# Integrators_SarSol.net
KiCad netlist of a schematic drawn in Altium Designer
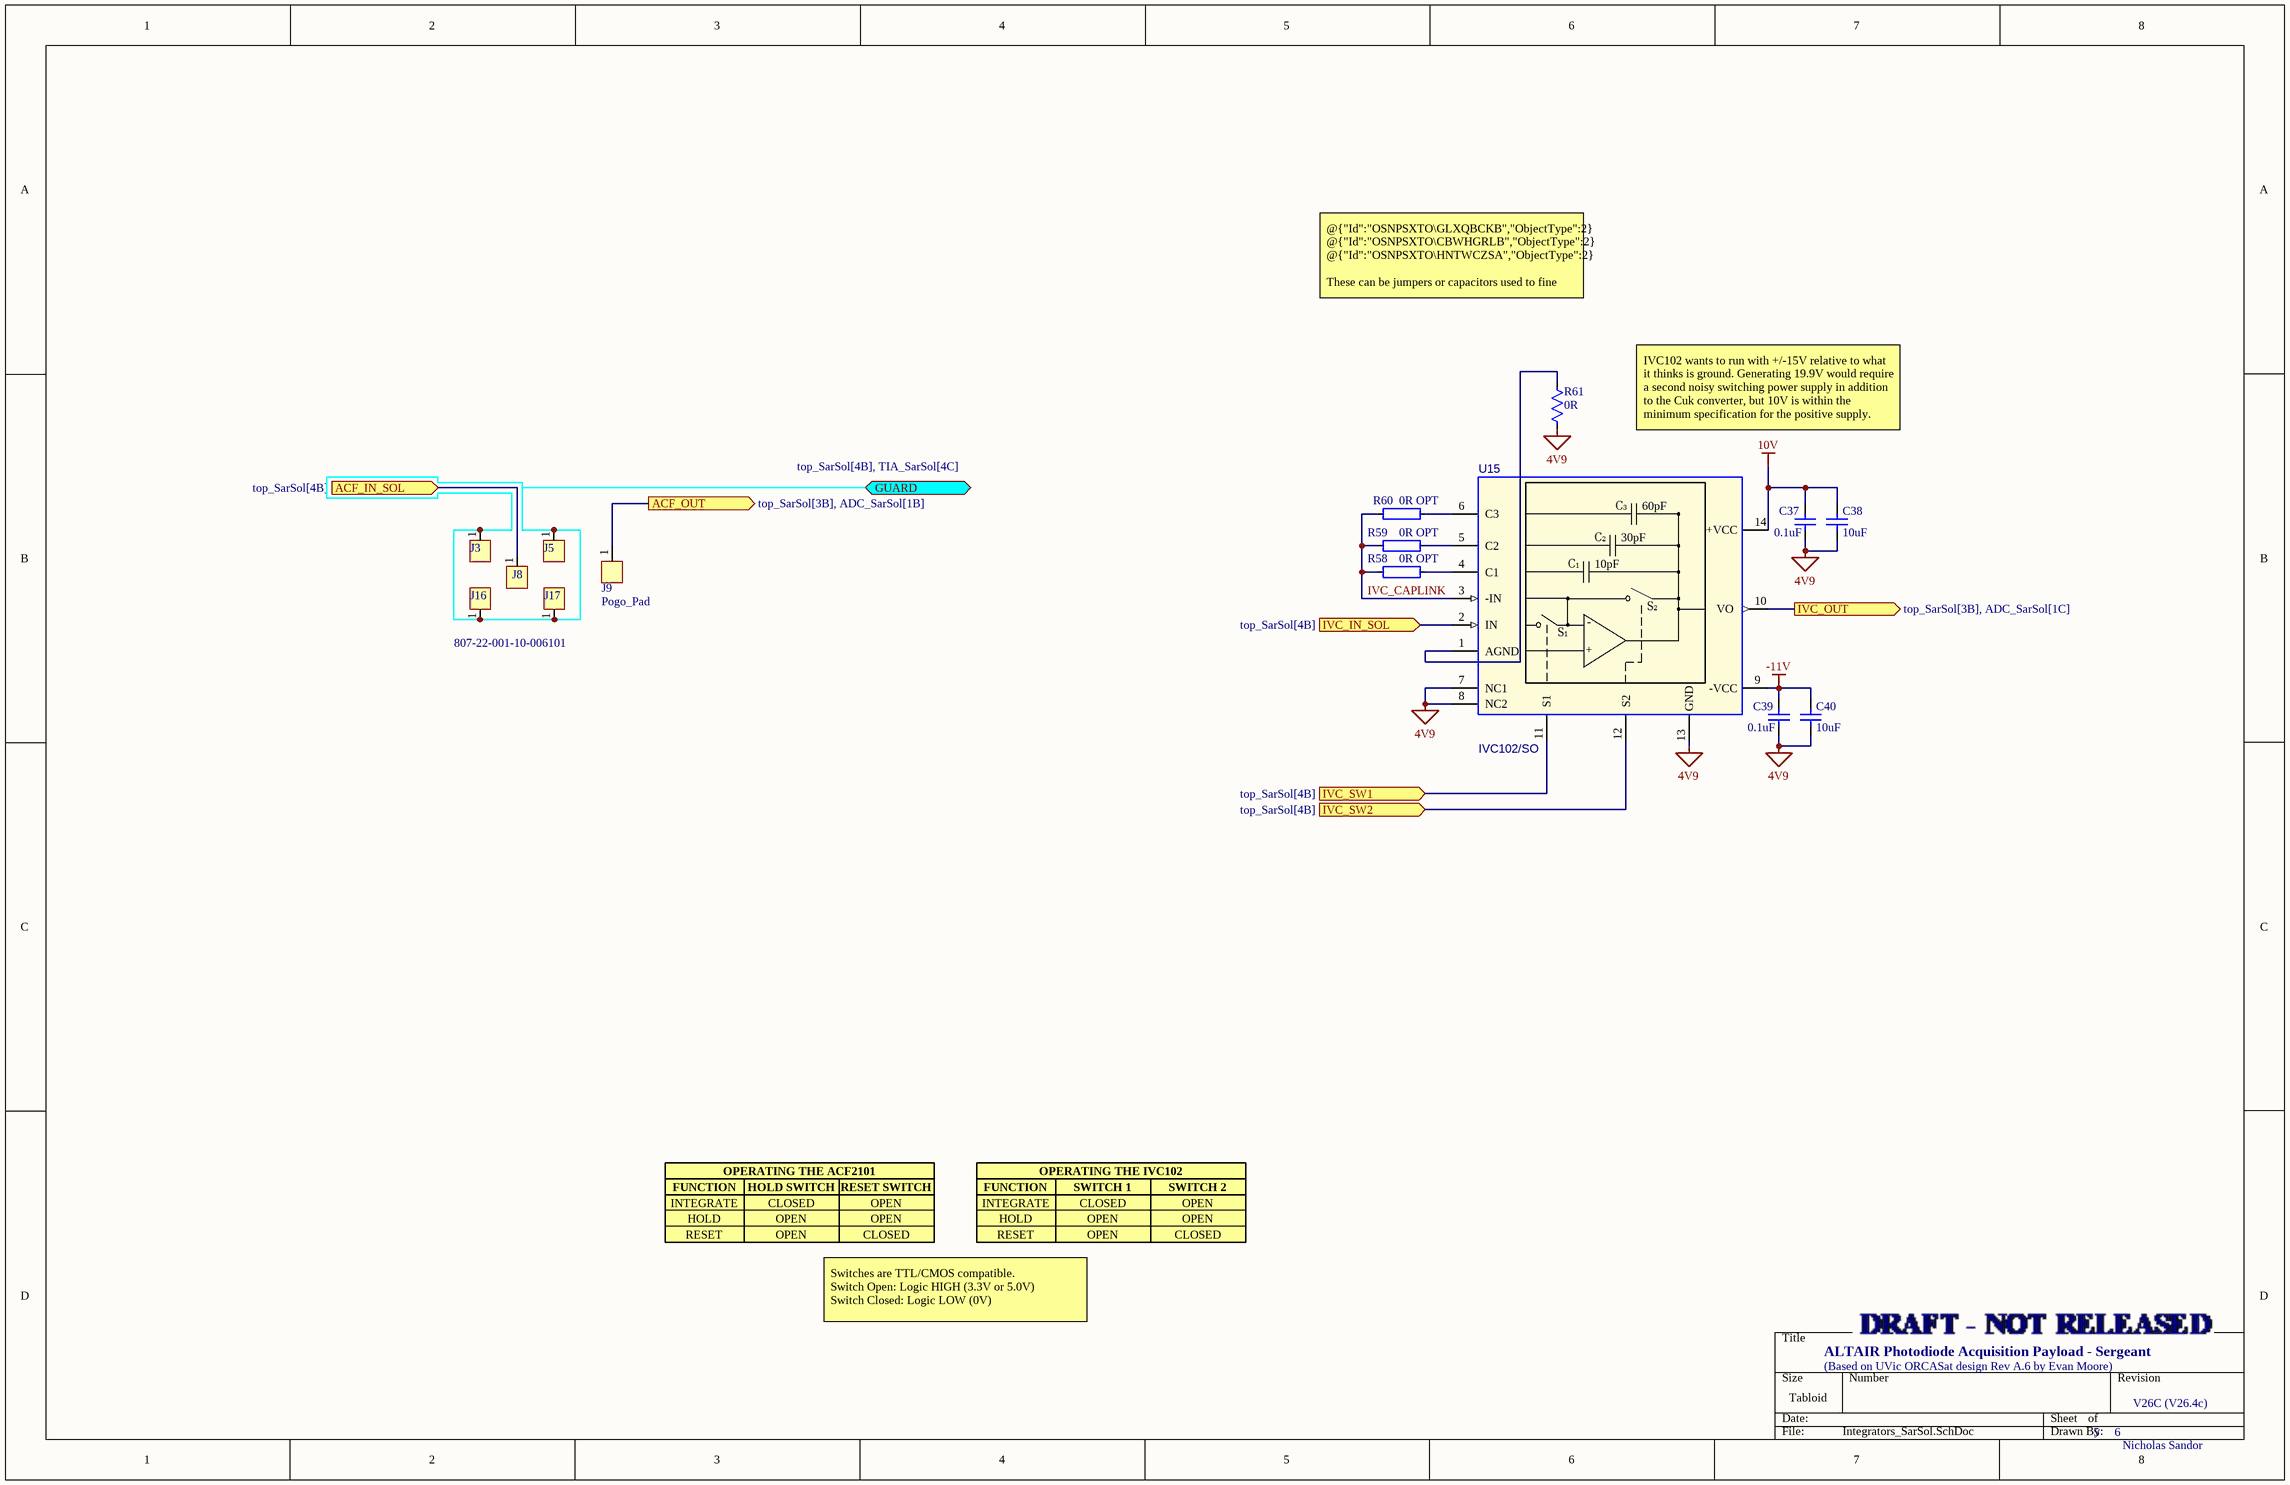
[diagram p0: Integrators_SarSol.SchDoc]

(export (version "E")
  (design (tool "Eeschema 10.0.6"))
  (components
    (comp (ref "C37")
      (value "0.1uF")
      (footprint "CAP 0603 NON-IPC KEMET X7R")
      (description "Kemet C0603C104K5RACAUTO - Cap Ceramic 0.1uF 50V X7R 10% 0603 125C Paper T/R")
      (fields (field (name "MF") "Kemet") (field (name "MP") "C0603C104K5RACAUTO"))
      (libsource (lib "ALTAIR_PD_Capacitors") (part "CAP"))
    )
    (comp (ref "C38")
      (value "10uF")
      (footprint "CAP 0805 IPC MID DENSITY")
      (description "Murata GRM21BR61E106KA73L - Cap Ceramic 10uF 10% 25V X5R 0805")
      (fields (field (name "MF") "Murata") (field (name "MP") "GRM21BR61E106KA73L"))
      (libsource (lib "ALTAIR_PD_Capacitors") (part "CAP"))
    )
    (comp (ref "C39")
      (value "0.1uF")
      (footprint "CAP 0603 NON-IPC KEMET X7R")
      (description "Kemet C0603C104K5RACAUTO - Cap Ceramic 0.1uF 50V X7R 10% 0603 125C Paper T/R")
      (fields (field (name "MF") "Kemet") (field (name "MP") "C0603C104K5RACAUTO"))
      (libsource (lib "ALTAIR_PD_Capacitors") (part "CAP"))
    )
    (comp (ref "C40")
      (value "10uF")
      (footprint "CAP 0805 IPC MID DENSITY")
      (description "Murata GRM21BR61E106KA73L - Cap Ceramic 10uF 10% 25V X5R 0805")
      (fields (field (name "MF") "Murata") (field (name "MP") "GRM21BR61E106KA73L"))
      (libsource (lib "ALTAIR_PD_Capacitors") (part "CAP"))
    )
    (comp (ref "J3")
      (value "807-22-001-10-006101")
      (footprint "POGO PIN 807-22-001-10-006101")
      (description "Mill-Max Individual Insulated Pin 5.99mm Initial Height")
      (fields (field (name "MF") "Mill-Max"))
      (libsource (lib "ALTAIR_PD_Pogo") (part "807-22-001-10-006101"))
    )
    (comp (ref "J5")
      (value "807-22-001-10-006101")
      (footprint "POGO PIN 807-22-001-10-006101")
      (description "Mill-Max Individual Insulated Pin 5.99mm Initial Height")
      (fields (field (name "MF") "Mill-Max"))
      (libsource (lib "ALTAIR_PD_Pogo") (part "807-22-001-10-006101"))
    )
    (comp (ref "J8")
      (value "807-22-001-10-006101")
      (footprint "POGO PIN 807-22-001-10-006101")
      (description "Mill-Max Individual Insulated Pin 5.99mm Initial Height")
      (fields (field (name "MF") "Mill-Max"))
      (libsource (lib "ALTAIR_PD_Pogo") (part "807-22-001-10-006101"))
    )
    (comp (ref "J9")
      (value "Pogo_Pad")
      (footprint "POGO PAD SOLDIER")
      (description "Pad for Pogo Pin without Guard")
      (libsource (lib "ALTAIR_PD_Pogo") (part "Pogo_Pad_NoGuard"))
    )
    (comp (ref "J16")
      (value "807-22-001-10-006101")
      (footprint "POGO PIN 807-22-001-10-006101")
      (description "Mill-Max Individual Insulated Pin 5.99mm Initial Height")
      (fields (field (name "MF") "Mill-Max"))
      (libsource (lib "") (part "807-22-001-10-006101_1"))
    )
    (comp (ref "J17")
      (value "807-22-001-10-006101")
      (footprint "POGO PIN 807-22-001-10-006101")
      (description "Mill-Max Individual Insulated Pin 5.99mm Initial Height")
      (fields (field (name "MF") "Mill-Max"))
      (libsource (lib "") (part "807-22-001-10-006101_1"))
    )
    (comp (ref "R58")
      (value "0R OPT")
      (footprint "RES 0402 IPC LOW DENSITY")
      (description "Yageo RC0402JR-070RL - Res 0 Ohms 1/16W SMD 0402")
      (fields (field (name "MF") "YAGEO") (field (name "MP") "RC0402JR-070RL"))
      (libsource (lib "ALTAIR_PD_Resistors") (part "IMPEDANCE"))
    )
    (comp (ref "R59")
      (value "0R OPT")
      (footprint "RES 0402 IPC LOW DENSITY")
      (description "Yageo RC0402JR-070RL - Res 0 Ohms 1/16W SMD 0402")
      (fields (field (name "MF") "YAGEO") (field (name "MP") "RC0402JR-070RL"))
      (libsource (lib "ALTAIR_PD_Resistors") (part "IMPEDANCE"))
    )
    (comp (ref "R60")
      (value "0R OPT")
      (footprint "RES 0402 IPC LOW DENSITY")
      (description "Yageo RC0402JR-070RL - Res 0 Ohms 1/16W SMD 0402")
      (fields (field (name "MF") "YAGEO") (field (name "MP") "RC0402JR-070RL"))
      (libsource (lib "ALTAIR_PD_Resistors") (part "IMPEDANCE"))
    )
    (comp (ref "R61")
      (value "0R")
      (footprint "RES 0402 IPC MID DENSITY")
      (description "Yageo RC0402JR-070RL - Res 0 Ohms 1/16W SMD 0402")
      (fields (field (name "MF") "YAGEO") (field (name "MP") "RC0402JR-070RL"))
      (libsource (lib "ALTAIR_PD_Resistors") (part "RES"))
    )
    (comp (ref "U15")
      (value "IVC102/SO")
      (footprint "14-SOIC 4MM WIDE LOW DENSITY")
      (description "Precision Switched Integrator Transimpedance Amplifier")
      (fields (field (name "MF") "Texas Instruments") (field (name "MP") "IVC102U"))
      (libsource (lib "ALTAIR_PD_Amplifiers") (part "IVC102/SO_5"))
    )
  )
  (nets
    (net (code "1") (name "-11V") (class "Default")
      (node (ref "C39") (pin "2") (pinfunction "2_2") (pintype "passive"))
      (node (ref "C40") (pin "2") (pinfunction "2_2") (pintype "passive"))
      (node (ref "U15") (pin "9") (pinfunction "-VCC_9") (pintype "power_in"))
    )
    (net (code "2") (name "/ACF_IN_SOL") (class "Default")
      (node (ref "J8") (pin "1") (pinfunction "1_1") (pintype "passive"))
    )
    (net (code "3") (name "/ACF_OUT") (class "Default")
      (node (ref "J9") (pin "1") (pinfunction "1_1") (pintype "passive"))
    )
    (net (code "4") (name "/GUARD") (class "Default")
      (node (ref "J16") (pin "1") (pinfunction "1_1") (pintype "passive"))
      (node (ref "J17") (pin "1") (pinfunction "1_1") (pintype "passive"))
      (node (ref "J3") (pin "1") (pinfunction "1_1") (pintype "passive"))
      (node (ref "J5") (pin "1") (pinfunction "1_1") (pintype "passive"))
    )
    (net (code "5") (name "/IVC_CAPLINK") (class "Default")
      (node (ref "R58") (pin "1") (pinfunction "1_1") (pintype "passive"))
      (node (ref "R59") (pin "1") (pinfunction "1_1") (pintype "passive"))
      (node (ref "R60") (pin "1") (pinfunction "1_1") (pintype "passive"))
      (node (ref "U15") (pin "3") (pinfunction "-IN_3") (pintype "input"))
    )
    (net (code "6") (name "/IVC_IN_SOL") (class "Default")
      (node (ref "U15") (pin "2") (pinfunction "IN_2") (pintype "input"))
    )
    (net (code "7") (name "/IVC_OUT") (class "Default")
      (node (ref "U15") (pin "10") (pinfunction "VO_10") (pintype "output"))
    )
    (net (code "8") (name "/IVC_SW1") (class "Default")
      (node (ref "U15") (pin "11") (pinfunction "S1_11") (pintype "passive"))
    )
    (net (code "9") (name "/IVC_SW2") (class "Default")
      (node (ref "U15") (pin "12") (pinfunction "S2_12") (pintype "passive"))
    )
    (net (code "10") (name "4V9") (class "Default")
      (node (ref "C37") (pin "1") (pinfunction "1_1") (pintype "passive"))
      (node (ref "C38") (pin "1") (pinfunction "1_1") (pintype "passive"))
      (node (ref "C39") (pin "1") (pinfunction "1_1") (pintype "passive"))
      (node (ref "C40") (pin "1") (pinfunction "1_1") (pintype "passive"))
      (node (ref "R61") (pin "2") (pinfunction "2_2") (pintype "passive"))
      (node (ref "U15") (pin "13") (pinfunction "GND_13") (pintype "power_in"))
      (node (ref "U15") (pin "7") (pinfunction "NC1_7") (pintype "passive"))
      (node (ref "U15") (pin "8") (pinfunction "NC2_8") (pintype "passive"))
    )
    (net (code "11") (name "10V") (class "Default")
      (node (ref "C37") (pin "2") (pinfunction "2_2") (pintype "passive"))
      (node (ref "C38") (pin "2") (pinfunction "2_2") (pintype "passive"))
      (node (ref "U15") (pin "14") (pinfunction "+VCC_14") (pintype "power_in"))
    )
    (net (code "12") (name "Net-(U15-AGND)") (class "Default")
      (node (ref "R61") (pin "1") (pinfunction "1_1") (pintype "passive"))
      (node (ref "U15") (pin "1") (pinfunction "AGND_1") (pintype "power_in"))
    )
    (net (code "13") (name "Net-(U15-C1)") (class "Default")
      (node (ref "R58") (pin "2") (pinfunction "2_2") (pintype "passive"))
      (node (ref "U15") (pin "4") (pinfunction "C1_4") (pintype "passive"))
    )
    (net (code "14") (name "Net-(U15-C2)") (class "Default")
      (node (ref "R59") (pin "2") (pinfunction "2_2") (pintype "passive"))
      (node (ref "U15") (pin "5") (pinfunction "C2_5") (pintype "passive"))
    )
    (net (code "15") (name "Net-(U15-C3)") (class "Default")
      (node (ref "R60") (pin "2") (pinfunction "2_2") (pintype "passive"))
      (node (ref "U15") (pin "6") (pinfunction "C3_6") (pintype "passive"))
    )
  )
)
